# main-schem-v1.net
KiCad netlist of a schematic drawn in Altium Designer
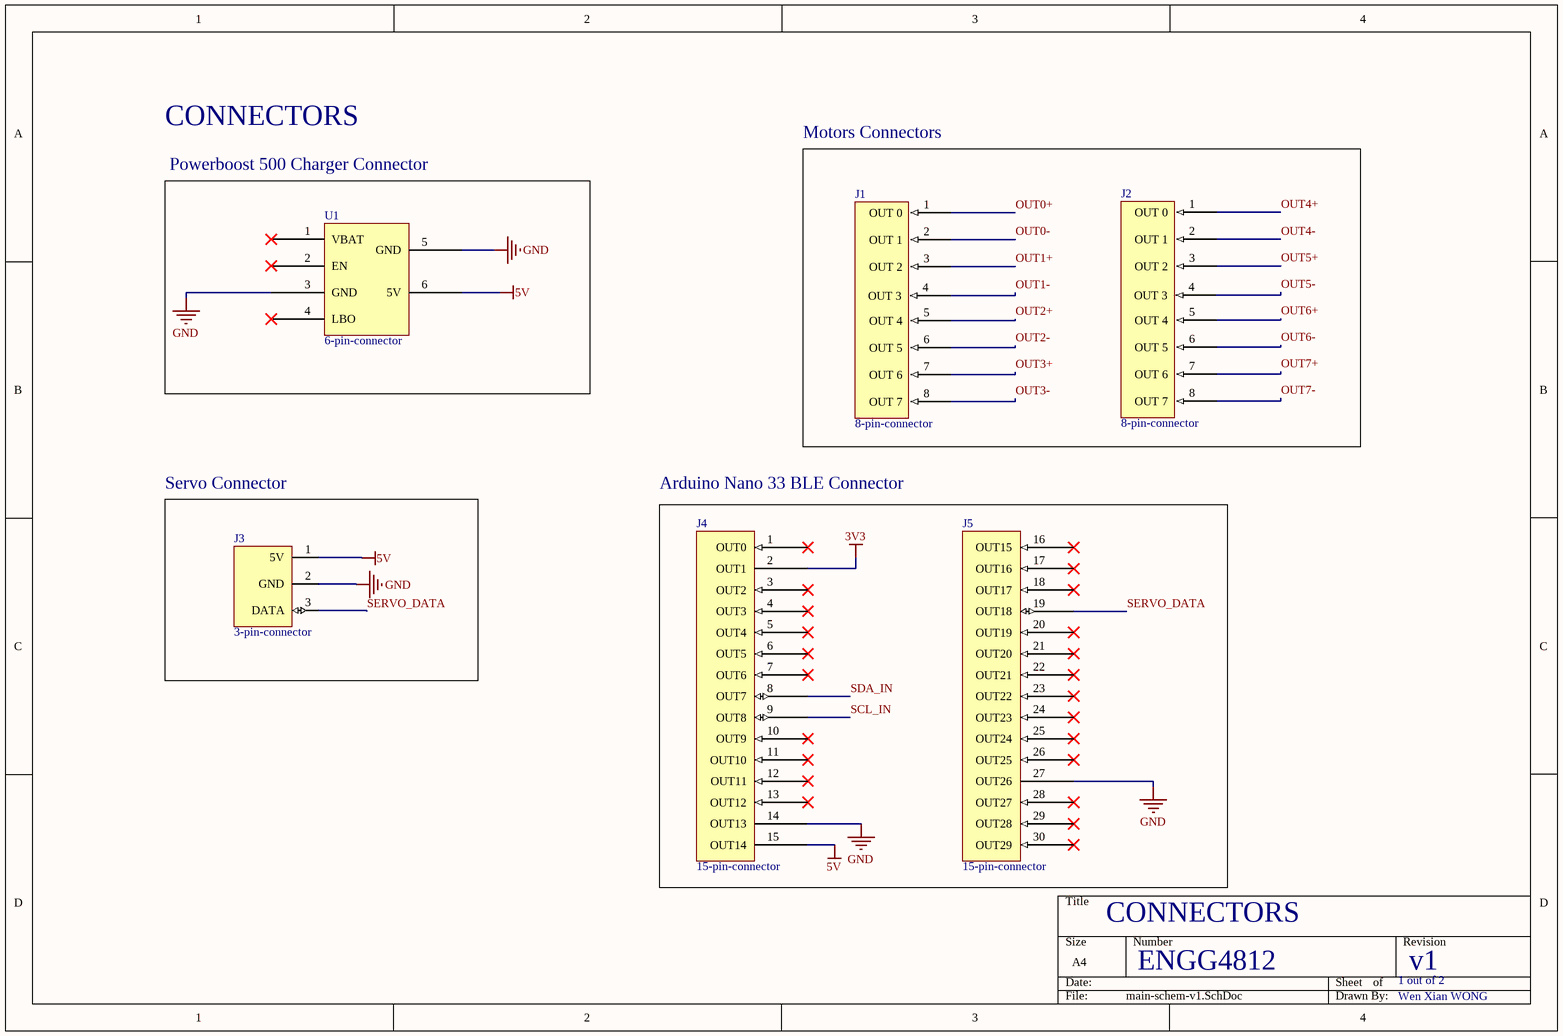
[diagram p0: main-schem-v1.SchDoc]

(export (version "E")
  (design (tool "Eeschema 10.0.6"))
  (components
    (comp (ref "J1")
      (value "8-pin-connector")
      (footprint "8-PIN-CONNECTOR")
      (libsource (lib "Schlib1") (part "8-pin-connector"))
    )
    (comp (ref "J2")
      (value "8-pin-connector")
      (footprint "8-PIN-CONNECTOR")
      (libsource (lib "Schlib1") (part "8-pin-connector"))
    )
    (comp (ref "J3")
      (value "3-pin-connector")
      (footprint "3-pin-connector - duplicate")
      (libsource (lib "Schlib1") (part "3-pin-connector"))
    )
    (comp (ref "J4")
      (value "15-pin-connector")
      (footprint "15-PIN-CONNECTOR  a - duplicate")
      (libsource (lib "Schlib1") (part "15-pin-connector"))
    )
    (comp (ref "J5")
      (value "15-pin-connector")
      (footprint "15-PIN-CONNECTOR b - duplicate")
      (libsource (lib "Schlib1") (part "15-pin-connector b"))
    )
    (comp (ref "U1")
      (value "6-pin-connector")
      (footprint "PowerBoost 500")
      (libsource (lib "Schlib1") (part "Powerboost 500"))
    )
  )
  (nets
    (net (code "1") (name "/OUT0+") (class "Default")
      (node (ref "J1") (pin "1") (pinfunction "OUT_0_1") (pintype "input"))
    )
    (net (code "2") (name "/OUT0-") (class "Default")
      (node (ref "J1") (pin "2") (pinfunction "OUT_1_2") (pintype "input"))
    )
    (net (code "3") (name "/OUT1+") (class "Default")
      (node (ref "J1") (pin "3") (pinfunction "OUT_2_3") (pintype "input"))
    )
    (net (code "4") (name "/OUT1-") (class "Default")
      (node (ref "J1") (pin "4") (pinfunction "OUT_3_4") (pintype "input"))
    )
    (net (code "5") (name "/OUT2+") (class "Default")
      (node (ref "J1") (pin "5") (pinfunction "OUT_4_5") (pintype "input"))
    )
    (net (code "6") (name "/OUT2-") (class "Default")
      (node (ref "J1") (pin "6") (pinfunction "OUT_5_6") (pintype "input"))
    )
    (net (code "7") (name "/OUT3+") (class "Default")
      (node (ref "J1") (pin "7") (pinfunction "OUT_6_7") (pintype "input"))
    )
    (net (code "8") (name "/OUT3-") (class "Default")
      (node (ref "J1") (pin "8") (pinfunction "OUT_7_8") (pintype "input"))
    )
    (net (code "9") (name "/OUT4+") (class "Default")
      (node (ref "J2") (pin "1") (pinfunction "OUT_0_1") (pintype "input"))
    )
    (net (code "10") (name "/OUT4-") (class "Default")
      (node (ref "J2") (pin "2") (pinfunction "OUT_1_2") (pintype "input"))
    )
    (net (code "11") (name "/OUT5+") (class "Default")
      (node (ref "J2") (pin "3") (pinfunction "OUT_2_3") (pintype "input"))
    )
    (net (code "12") (name "/OUT5-") (class "Default")
      (node (ref "J2") (pin "4") (pinfunction "OUT_3_4") (pintype "input"))
    )
    (net (code "13") (name "/OUT6+") (class "Default")
      (node (ref "J2") (pin "5") (pinfunction "OUT_4_5") (pintype "input"))
    )
    (net (code "14") (name "/OUT6-") (class "Default")
      (node (ref "J2") (pin "6") (pinfunction "OUT_5_6") (pintype "input"))
    )
    (net (code "15") (name "/OUT7+") (class "Default")
      (node (ref "J2") (pin "7") (pinfunction "OUT_6_7") (pintype "input"))
    )
    (net (code "16") (name "/OUT7-") (class "Default")
      (node (ref "J2") (pin "8") (pinfunction "OUT_7_8") (pintype "input"))
    )
    (net (code "17") (name "/SCL_IN") (class "Default")
      (node (ref "J4") (pin "9") (pinfunction "OUT8_9") (pintype "bidirectional"))
    )
    (net (code "18") (name "/SDA_IN") (class "Default")
      (node (ref "J4") (pin "8") (pinfunction "OUT7_8") (pintype "bidirectional"))
    )
    (net (code "19") (name "/SERVO_DATA") (class "Default")
      (node (ref "J3") (pin "3") (pinfunction "DATA_3") (pintype "bidirectional"))
      (node (ref "J5") (pin "19") (pinfunction "OUT18_19") (pintype "bidirectional"))
    )
    (net (code "20") (name "3V3") (class "Default")
      (node (ref "J4") (pin "2") (pinfunction "OUT1_2") (pintype "passive"))
    )
    (net (code "21") (name "5V") (class "Default")
      (node (ref "J3") (pin "1") (pinfunction "5V_1") (pintype "power_in"))
      (node (ref "J4") (pin "15") (pinfunction "OUT14_15") (pintype "power_in"))
      (node (ref "U1") (pin "6") (pinfunction "5V_6") (pintype "power_in"))
    )
    (net (code "22") (name "GND") (class "Default")
      (node (ref "J3") (pin "2") (pinfunction "GND_2") (pintype "passive"))
      (node (ref "J4") (pin "14") (pinfunction "OUT13_14") (pintype "passive"))
      (node (ref "J5") (pin "27") (pinfunction "OUT26_27") (pintype "passive"))
      (node (ref "U1") (pin "3") (pinfunction "GND_3") (pintype "passive"))
      (node (ref "U1") (pin "5") (pinfunction "GND_5") (pintype "passive"))
    )
    (net (code "23") (name "unconnected-(J4-OUT0-Pad1)") (class "Default")
      (node (ref "J4") (pin "1") (pinfunction "OUT0_1") (pintype "input+no_connect"))
    )
    (net (code "24") (name "unconnected-(J4-OUT2-Pad3)") (class "Default")
      (node (ref "J4") (pin "3") (pinfunction "OUT2_3") (pintype "input+no_connect"))
    )
    (net (code "25") (name "unconnected-(J4-OUT3-Pad4)") (class "Default")
      (node (ref "J4") (pin "4") (pinfunction "OUT3_4") (pintype "input+no_connect"))
    )
    (net (code "26") (name "unconnected-(J4-OUT4-Pad5)") (class "Default")
      (node (ref "J4") (pin "5") (pinfunction "OUT4_5") (pintype "input+no_connect"))
    )
    (net (code "27") (name "unconnected-(J4-OUT5-Pad6)") (class "Default")
      (node (ref "J4") (pin "6") (pinfunction "OUT5_6") (pintype "input+no_connect"))
    )
    (net (code "28") (name "unconnected-(J4-OUT6-Pad7)") (class "Default")
      (node (ref "J4") (pin "7") (pinfunction "OUT6_7") (pintype "input+no_connect"))
    )
    (net (code "29") (name "unconnected-(J4-OUT9-Pad10)") (class "Default")
      (node (ref "J4") (pin "10") (pinfunction "OUT9_10") (pintype "input+no_connect"))
    )
    (net (code "30") (name "unconnected-(J4-OUT10-Pad11)") (class "Default")
      (node (ref "J4") (pin "11") (pinfunction "OUT10_11") (pintype "input+no_connect"))
    )
    (net (code "31") (name "unconnected-(J4-OUT11-Pad12)") (class "Default")
      (node (ref "J4") (pin "12") (pinfunction "OUT11_12") (pintype "input+no_connect"))
    )
    (net (code "32") (name "unconnected-(J4-OUT12-Pad13)") (class "Default")
      (node (ref "J4") (pin "13") (pinfunction "OUT12_13") (pintype "input+no_connect"))
    )
    (net (code "33") (name "unconnected-(J5-OUT15-Pad16)") (class "Default")
      (node (ref "J5") (pin "16") (pinfunction "OUT15_16") (pintype "input+no_connect"))
    )
    (net (code "34") (name "unconnected-(J5-OUT16-Pad17)") (class "Default")
      (node (ref "J5") (pin "17") (pinfunction "OUT16_17") (pintype "input+no_connect"))
    )
    (net (code "35") (name "unconnected-(J5-OUT17-Pad18)") (class "Default")
      (node (ref "J5") (pin "18") (pinfunction "OUT17_18") (pintype "input+no_connect"))
    )
    (net (code "36") (name "unconnected-(J5-OUT19-Pad20)") (class "Default")
      (node (ref "J5") (pin "20") (pinfunction "OUT19_20") (pintype "input+no_connect"))
    )
    (net (code "37") (name "unconnected-(J5-OUT20-Pad21)") (class "Default")
      (node (ref "J5") (pin "21") (pinfunction "OUT20_21") (pintype "input+no_connect"))
    )
    (net (code "38") (name "unconnected-(J5-OUT21-Pad22)") (class "Default")
      (node (ref "J5") (pin "22") (pinfunction "OUT21_22") (pintype "input+no_connect"))
    )
    (net (code "39") (name "unconnected-(J5-OUT22-Pad23)") (class "Default")
      (node (ref "J5") (pin "23") (pinfunction "OUT22_23") (pintype "input+no_connect"))
    )
    (net (code "40") (name "unconnected-(J5-OUT23-Pad24)") (class "Default")
      (node (ref "J5") (pin "24") (pinfunction "OUT23_24") (pintype "input+no_connect"))
    )
    (net (code "41") (name "unconnected-(J5-OUT24-Pad25)") (class "Default")
      (node (ref "J5") (pin "25") (pinfunction "OUT24_25") (pintype "input+no_connect"))
    )
    (net (code "42") (name "unconnected-(J5-OUT25-Pad26)") (class "Default")
      (node (ref "J5") (pin "26") (pinfunction "OUT25_26") (pintype "input+no_connect"))
    )
    (net (code "43") (name "unconnected-(J5-OUT27-Pad28)") (class "Default")
      (node (ref "J5") (pin "28") (pinfunction "OUT27_28") (pintype "input+no_connect"))
    )
    (net (code "44") (name "unconnected-(J5-OUT28-Pad29)") (class "Default")
      (node (ref "J5") (pin "29") (pinfunction "OUT28_29") (pintype "input+no_connect"))
    )
    (net (code "45") (name "unconnected-(J5-OUT29-Pad30)") (class "Default")
      (node (ref "J5") (pin "30") (pinfunction "OUT29_30") (pintype "input+no_connect"))
    )
    (net (code "46") (name "unconnected-(U1-EN-Pad2)") (class "Default")
      (node (ref "U1") (pin "2") (pinfunction "EN_2") (pintype "passive+no_connect"))
    )
    (net (code "47") (name "unconnected-(U1-LBO-Pad4)") (class "Default")
      (node (ref "U1") (pin "4") (pinfunction "LBO_4") (pintype "passive+no_connect"))
    )
    (net (code "48") (name "unconnected-(U1-VBAT-Pad1)") (class "Default")
      (node (ref "U1") (pin "1") (pinfunction "VBAT_1") (pintype "power_in+no_connect"))
    )
  )
)
